# SensorsOnly_v6.net
KiCad netlist of a schematic drawn in EAGLE
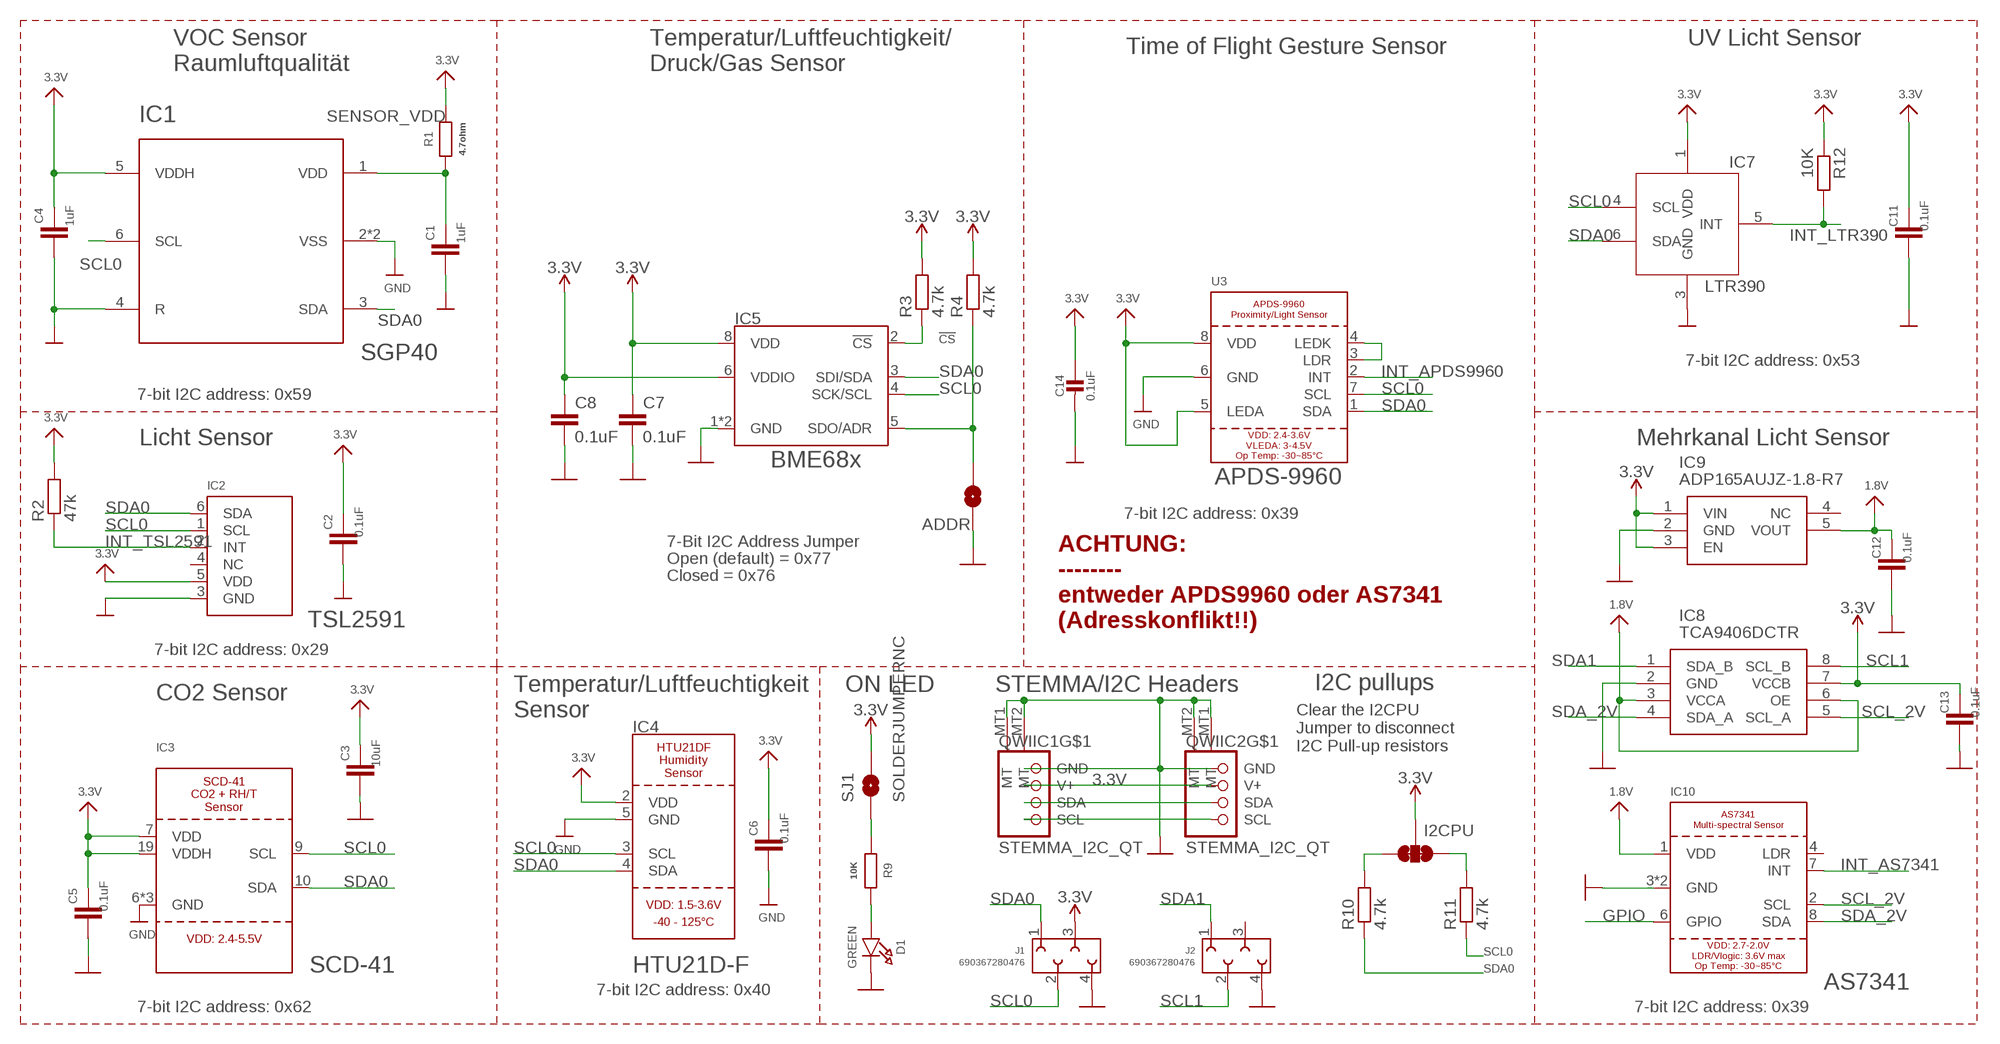
[diagram p0: schematic, sheet 1]

(export (version "E")
  (design (tool "Eeschema 10.0.6"))
  (components
    (comp (ref "ADDR")
      (value "JUMPER-SMT_2_NO_SILK")
      (footprint "eagle-import:SMT-JUMPER_2_NO_SILK")
      (libsource (lib "eagle-import") (part "JUMPER-SMT_2_NO_SILK"))
    )
    (comp (ref "C1")
      (value "1uF")
      (footprint "eagle-import:C0805")
      (libsource (lib "eagle-import") (part "C-EUC0805"))
    )
    (comp (ref "C2")
      (value "0.1uF")
      (footprint "eagle-import:C0603")
      (libsource (lib "eagle-import") (part "C-EUC0603"))
    )
    (comp (ref "C3")
      (value "10uF")
      (footprint "eagle-import:C0805")
      (libsource (lib "eagle-import") (part "C-EUC0805"))
    )
    (comp (ref "C4")
      (value "1uF")
      (footprint "eagle-import:C0805")
      (libsource (lib "eagle-import") (part "C-EUC0805"))
    )
    (comp (ref "C5")
      (value "0.1uF")
      (footprint "eagle-import:C0603")
      (libsource (lib "eagle-import") (part "C-EUC0603"))
    )
    (comp (ref "C6")
      (value "0.1uF")
      (footprint "eagle-import:C0603")
      (libsource (lib "eagle-import") (part "C-EUC0603"))
    )
    (comp (ref "C7")
      (value "0.1uF")
      (footprint "eagle-import:C0603")
      (libsource (lib "eagle-import") (part "C-EUC0603"))
    )
    (comp (ref "C8")
      (value "0.1uF")
      (footprint "eagle-import:C0603")
      (libsource (lib "eagle-import") (part "C-EUC0603"))
    )
    (comp (ref "C11")
      (value "0.1uF")
      (footprint "eagle-import:C0603")
      (libsource (lib "eagle-import") (part "C-EUC0603"))
    )
    (comp (ref "C12")
      (value "0.1uF")
      (footprint "eagle-import:C0603")
      (libsource (lib "eagle-import") (part "C-EUC0603"))
    )
    (comp (ref "C13")
      (value "0.1uF")
      (footprint "eagle-import:C0603")
      (libsource (lib "eagle-import") (part "C-EUC0603"))
    )
    (comp (ref "C14")
      (value "0.1uF")
      (footprint "eagle-import:0603-NO")
      (libsource (lib "eagle-import") (part "CAP_CERAMIC0603_NO"))
    )
    (comp (ref "D1")
      (value "GREEN")
      (footprint "eagle-import:CHIPLED_0603_NOOUTLINE")
      (libsource (lib "eagle-import") (part "LED0603_NOOUTLINE"))
    )
    (comp (ref "I2CPU")
      (value "I2C PU")
      (footprint "eagle-import:SMT-JUMPER_3_2-NC_TRACE_SILK")
      (libsource (lib "eagle-import") (part "JUMPER-SMT_3_2-NC_TRACE_SILK"))
    )
    (comp (ref "IC1")
      (value "SGP40")
      (footprint "eagle-import:SGP30")
      (libsource (lib "eagle-import") (part "SGP30"))
    )
    (comp (ref "IC2")
      (value "TSL2591")
      (footprint "eagle-import:DFN6_TAOS")
      (libsource (lib "eagle-import") (part "LIGHT_TSL2591"))
    )
    (comp (ref "IC3")
      (value "SCD-41")
      (footprint "eagle-import:SCD41")
      (libsource (lib "eagle-import") (part "SCD-41"))
    )
    (comp (ref "IC4")
      (value "HTU21D-F")
      (footprint "eagle-import:HTU21DF")
      (libsource (lib "eagle-import") (part "HTU21DF"))
    )
    (comp (ref "IC5")
      (value "BME680 Air Quality Sensor")
      (footprint "eagle-import:LGA3.0X3.0")
      (libsource (lib "eagle-import") (part "BME680-LGA"))
    )
    (comp (ref "IC7")
      (value "LTR390")
      (footprint "eagle-import:LTR390")
      (libsource (lib "eagle-import") (part "LTR390"))
    )
    (comp (ref "IC8")
      (value "TCA9406DCTR")
      (footprint "eagle-import:SOP65P400X130-8N")
      (fields (field (name "MOUSER_PART_NUMBER") "595-TCA9406DCTR"))
      (libsource (lib "eagle-import") (part "TCA9406DCTR"))
    )
    (comp (ref "IC9")
      (value "ADP165AUJZ-1.8-R7")
      (footprint "eagle-import:SOT95P280X100-5N")
      (fields
        (field (name "MANUFACTURER_PART_NUMBER") "ADP165AUJZ-3.3-R7")
        (field (name "MOUSER_PART_NUMBER") "584-ADP165AUJZ3.3R7")
      )
      (libsource (lib "eagle-import") (part "ADP165AUJZ-3.3-R7"))
    )
    (comp (ref "IC10")
      (value "AS7341")
      (footprint "eagle-import:AS7341")
      (libsource (lib "eagle-import") (part "AS7341"))
    )
    (comp (ref "J1")
      (value "690367280476")
      (footprint "eagle-import:690367280476")
      (libsource (lib "eagle-import") (part "690367280476"))
    )
    (comp (ref "J2")
      (value "690367280476")
      (footprint "eagle-import:690367280476")
      (libsource (lib "eagle-import") (part "690367280476"))
    )
    (comp (ref "QWIIC1")
      (value "STEMMA_I2C_QT")
      (footprint "eagle-import:JST_SH4")
      (libsource (lib "eagle-import") (part "STEMMA_I2C_QT"))
    )
    (comp (ref "QWIIC2")
      (value "STEMMA_I2C_QT")
      (footprint "eagle-import:JST_SH4")
      (libsource (lib "eagle-import") (part "STEMMA_I2C_QT"))
    )
    (comp (ref "R1")
      (value "4.7ohm")
      (footprint "eagle-import:R0603")
      (libsource (lib "eagle-import") (part "R-EU_R0603"))
    )
    (comp (ref "R2")
      (value "47k")
      (footprint "eagle-import:R0603")
      (libsource (lib "eagle-import") (part "R-EU_R0603"))
    )
    (comp (ref "R3")
      (value "4.7k")
      (footprint "eagle-import:R0603")
      (libsource (lib "eagle-import") (part "R-EU_R0603"))
    )
    (comp (ref "R4")
      (value "4.7k")
      (footprint "eagle-import:R0603")
      (libsource (lib "eagle-import") (part "R-EU_R0603"))
    )
    (comp (ref "R9")
      (value "10K")
      (footprint "eagle-import:R0603")
      (libsource (lib "eagle-import") (part "R-EU_R0603"))
    )
    (comp (ref "R10")
      (value "4.7k")
      (footprint "eagle-import:R0603")
      (libsource (lib "eagle-import") (part "R-EU_R0603"))
    )
    (comp (ref "R11")
      (value "4.7k")
      (footprint "eagle-import:R0603")
      (libsource (lib "eagle-import") (part "R-EU_R0603"))
    )
    (comp (ref "R12")
      (value "10K")
      (footprint "eagle-import:R0603")
      (libsource (lib "eagle-import") (part "R-EU_R0603"))
    )
    (comp (ref "SJ1")
      (value "SOLDERJUMPERNC")
      (footprint "eagle-import:SJ_2S")
      (libsource (lib "eagle-import") (part "SOLDERJUMPERNC"))
    )
    (comp (ref "U3")
      (value "APDS-9960")
      (footprint "eagle-import:APDS-9960")
      (libsource (lib "eagle-import") (part "APDS-9960"))
    )
  )
  (nets
    (net (code "1") (name "/GPIO") (class "Default")
      (node (ref "IC10") (pin "6") (pinfunction "GPIO_6") (pintype "power_in"))
    )
    (net (code "2") (name "/INT_APDS9960") (class "Default")
      (node (ref "U3") (pin "2") (pinfunction "INT_2") (pintype "output"))
    )
    (net (code "3") (name "/INT_AS7341") (class "Default")
      (node (ref "IC10") (pin "7") (pinfunction "INT_7") (pintype "output"))
    )
    (net (code "4") (name "/INT_LTR390") (class "Default")
      (node (ref "IC7") (pin "5") (pinfunction "INT_5") (pintype "bidirectional"))
      (node (ref "R12") (pin "2") (pinfunction "2_2") (pintype "passive"))
    )
    (net (code "5") (name "/INT_TSL2591") (class "Default")
      (node (ref "IC2") (pin "2") (pinfunction "INT_2") (pintype "output"))
      (node (ref "R2") (pin "1") (pinfunction "1_1") (pintype "passive"))
    )
    (net (code "6") (name "/SCL1") (class "Default")
      (node (ref "IC8") (pin "8") (pinfunction "SCL_B_8") (pintype "bidirectional"))
      (node (ref "J2") (pin "2") (pinfunction "2_2") (pintype "passive"))
    )
    (net (code "7") (name "/SCL_2V") (class "Default")
      (node (ref "IC10") (pin "2") (pinfunction "SCL_2") (pintype "input"))
      (node (ref "IC8") (pin "5") (pinfunction "SCL_A_5") (pintype "bidirectional"))
    )
    (net (code "8") (name "/SDA1") (class "Default")
      (node (ref "IC8") (pin "1") (pinfunction "SDA_B_1") (pintype "bidirectional"))
      (node (ref "J2") (pin "1") (pinfunction "1_1") (pintype "passive"))
    )
    (net (code "9") (name "/SDA_2V") (class "Default")
      (node (ref "IC10") (pin "8") (pinfunction "SDA_8") (pintype "bidirectional"))
      (node (ref "IC8") (pin "4") (pinfunction "SDA_A_4") (pintype "bidirectional"))
    )
    (net (code "10") (name "/SENSOR_VDD") (class "Default")
      (node (ref "C1") (pin "1") (pinfunction "1_1") (pintype "passive"))
      (node (ref "IC1") (pin "1") (pinfunction "VDD_1") (pintype "bidirectional"))
      (node (ref "R1") (pin "1") (pinfunction "1_1") (pintype "passive"))
    )
    (net (code "11") (name "/~{CS}") (class "Default")
      (node (ref "IC5") (pin "2") (pinfunction "~{CS}_2") (pintype "bidirectional"))
      (node (ref "R3") (pin "1") (pinfunction "1_1") (pintype "passive"))
    )
    (net (code "12") (name "1.8V") (class "Default")
      (node (ref "C12") (pin "1") (pinfunction "1_1") (pintype "passive"))
      (node (ref "IC10") (pin "1") (pinfunction "VDD_1") (pintype "power_in"))
      (node (ref "IC8") (pin "3") (pinfunction "VCCA_3") (pintype "bidirectional"))
      (node (ref "IC8") (pin "6") (pinfunction "OE_6") (pintype "bidirectional"))
      (node (ref "IC9") (pin "5") (pinfunction "VOUT_5") (pintype "bidirectional"))
    )
    (net (code "13") (name "3.3V") (class "Default")
      (node (ref "C11") (pin "1") (pinfunction "1_1") (pintype "passive"))
      (node (ref "C13") (pin "1") (pinfunction "1_1") (pintype "passive"))
      (node (ref "C14") (pin "1") (pinfunction "1_1") (pintype "passive"))
      (node (ref "C2") (pin "1") (pinfunction "1_1") (pintype "passive"))
      (node (ref "C3") (pin "1") (pinfunction "1_1") (pintype "passive"))
      (node (ref "C4") (pin "1") (pinfunction "1_1") (pintype "passive"))
      (node (ref "C5") (pin "1") (pinfunction "1_1") (pintype "passive"))
      (node (ref "C6") (pin "1") (pinfunction "1_1") (pintype "passive"))
      (node (ref "C7") (pin "1") (pinfunction "1_1") (pintype "passive"))
      (node (ref "C8") (pin "1") (pinfunction "1_1") (pintype "passive"))
      (node (ref "I2CPU") (pin "2") (pinfunction "2_2") (pintype "passive"))
      (node (ref "IC1") (pin "5") (pinfunction "VDDH_5") (pintype "bidirectional"))
      (node (ref "IC2") (pin "5") (pinfunction "VDD_5") (pintype "power_in"))
      (node (ref "IC3") (pin "19") (pinfunction "VDDH_19") (pintype "power_in"))
      (node (ref "IC3") (pin "7") (pinfunction "VDD_7") (pintype "power_in"))
      (node (ref "IC4") (pin "2") (pinfunction "VDD_2") (pintype "power_in"))
      (node (ref "IC5") (pin "6") (pinfunction "VDDIO_6") (pintype "bidirectional"))
      (node (ref "IC5") (pin "8") (pinfunction "VDD_8") (pintype "bidirectional"))
      (node (ref "IC7") (pin "1") (pinfunction "VDD_1") (pintype "power_in"))
      (node (ref "IC8") (pin "7") (pinfunction "VCCB_7") (pintype "bidirectional"))
      (node (ref "IC9") (pin "1") (pinfunction "VIN_1") (pintype "bidirectional"))
      (node (ref "IC9") (pin "3") (pinfunction "EN_3") (pintype "bidirectional"))
      (node (ref "J1") (pin "3") (pinfunction "3_3") (pintype "passive"))
      (node (ref "QWIIC1") (pin "2") (pinfunction "V+_2") (pintype "passive"))
      (node (ref "QWIIC2") (pin "2") (pinfunction "V+_2") (pintype "passive"))
      (node (ref "R1") (pin "2") (pinfunction "2_2") (pintype "passive"))
      (node (ref "R12") (pin "1") (pinfunction "1_1") (pintype "passive"))
      (node (ref "R2") (pin "2") (pinfunction "2_2") (pintype "passive"))
      (node (ref "R3") (pin "2") (pinfunction "2_2") (pintype "passive"))
      (node (ref "R4") (pin "2") (pinfunction "2_2") (pintype "passive"))
      (node (ref "SJ1") (pin "2") (pinfunction "2_2") (pintype "passive"))
      (node (ref "U3") (pin "5") (pinfunction "LEDA_5") (pintype "power_in"))
      (node (ref "U3") (pin "8") (pinfunction "VDD_8") (pintype "power_in"))
    )
    (net (code "14") (name "GND") (class "Default")
      (node (ref "ADDR") (pin "1") (pinfunction "1_1") (pintype "passive"))
      (node (ref "C1") (pin "2") (pinfunction "2_2") (pintype "passive"))
      (node (ref "C11") (pin "2") (pinfunction "2_2") (pintype "passive"))
      (node (ref "C12") (pin "2") (pinfunction "2_2") (pintype "passive"))
      (node (ref "C13") (pin "2") (pinfunction "2_2") (pintype "passive"))
      (node (ref "C14") (pin "2") (pinfunction "2_2") (pintype "passive"))
      (node (ref "C2") (pin "2") (pinfunction "2_2") (pintype "passive"))
      (node (ref "C3") (pin "2") (pinfunction "2_2") (pintype "passive"))
      (node (ref "C4") (pin "2") (pinfunction "2_2") (pintype "passive"))
      (node (ref "C5") (pin "2") (pinfunction "2_2") (pintype "passive"))
      (node (ref "C6") (pin "2") (pinfunction "2_2") (pintype "passive"))
      (node (ref "C7") (pin "2") (pinfunction "2_2") (pintype "passive"))
      (node (ref "C8") (pin "2") (pinfunction "2_2") (pintype "passive"))
      (node (ref "D1") (pin "C") (pinfunction "C_C") (pintype "passive"))
      (node (ref "IC1") (pin "2") (pinfunction "VSS_2") (pintype "bidirectional"))
      (node (ref "IC1") (pin "4") (pinfunction "R_4") (pintype "bidirectional"))
      (node (ref "IC1") (pin "P$7") (pinfunction "VSS_P$7") (pintype "bidirectional"))
      (node (ref "IC10") (pin "3") (pinfunction "GND_3") (pintype "power_in"))
      (node (ref "IC10") (pin "5") (pinfunction "GND_5") (pintype "power_in"))
      (node (ref "IC2") (pin "3") (pinfunction "GND_3") (pintype "power_in"))
      (node (ref "IC3") (pin "20") (pinfunction "GND_20") (pintype "power_in"))
      (node (ref "IC3") (pin "6") (pinfunction "GND_6") (pintype "power_in"))
      (node (ref "IC3") (pin "P$1") (pinfunction "GND_P$1") (pintype "power_in"))
      (node (ref "IC4") (pin "5") (pinfunction "GND_5") (pintype "power_in"))
      (node (ref "IC5") (pin "1") (pinfunction "GND_1") (pintype "bidirectional"))
      (node (ref "IC5") (pin "7") (pinfunction "GND_7") (pintype "bidirectional"))
      (node (ref "IC7") (pin "3") (pinfunction "GND_3") (pintype "power_in"))
      (node (ref "IC8") (pin "2") (pinfunction "GND_2") (pintype "bidirectional"))
      (node (ref "IC9") (pin "2") (pinfunction "GND_2") (pintype "bidirectional"))
      (node (ref "J1") (pin "4") (pinfunction "4_4") (pintype "passive"))
      (node (ref "J2") (pin "4") (pinfunction "4_4") (pintype "passive"))
      (node (ref "QWIIC1") (pin "1") (pinfunction "GND_1") (pintype "passive"))
      (node (ref "QWIIC1") (pin "MT1") (pinfunction "MT_MT1") (pintype "bidirectional"))
      (node (ref "QWIIC1") (pin "MT2") (pinfunction "MT_MT2") (pintype "bidirectional"))
      (node (ref "QWIIC2") (pin "1") (pinfunction "GND_1") (pintype "passive"))
      (node (ref "QWIIC2") (pin "MT1") (pinfunction "MT_MT1") (pintype "bidirectional"))
      (node (ref "QWIIC2") (pin "MT2") (pinfunction "MT_MT2") (pintype "bidirectional"))
      (node (ref "U3") (pin "6") (pinfunction "GND_6") (pintype "power_in"))
    )
    (net (code "15") (name "Net-(D1-PadA)") (class "Default")
      (node (ref "D1") (pin "A") (pinfunction "A_A") (pintype "passive"))
      (node (ref "R9") (pin "2") (pinfunction "2_2") (pintype "passive"))
    )
    (net (code "16") (name "Net-(I2CPU-Pad1)") (class "Default")
      (node (ref "I2CPU") (pin "1") (pinfunction "1_1") (pintype "passive"))
      (node (ref "R11") (pin "2") (pinfunction "2_2") (pintype "passive"))
    )
    (net (code "17") (name "Net-(I2CPU-Pad3)") (class "Default")
      (node (ref "I2CPU") (pin "3") (pinfunction "3_3") (pintype "passive"))
      (node (ref "R10") (pin "2") (pinfunction "2_2") (pintype "passive"))
    )
    (net (code "18") (name "Net-(IC5-SDO{slash}ADR)") (class "Default")
      (node (ref "ADDR") (pin "2") (pinfunction "2_2") (pintype "passive"))
      (node (ref "IC5") (pin "5") (pinfunction "SDO/ADR_5") (pintype "bidirectional"))
      (node (ref "R4") (pin "1") (pinfunction "1_1") (pintype "passive"))
    )
    (net (code "19") (name "Net-(R9-Pad1)") (class "Default")
      (node (ref "R9") (pin "1") (pinfunction "1_1") (pintype "passive"))
      (node (ref "SJ1") (pin "1") (pinfunction "1_1") (pintype "passive"))
    )
    (net (code "20") (name "Net-(U3-LDR)") (class "Default")
      (node (ref "U3") (pin "3") (pinfunction "LDR_3") (pintype "bidirectional"))
      (node (ref "U3") (pin "4") (pinfunction "LEDK_4") (pintype "bidirectional"))
    )
    (net (code "21") (name "SCL0") (class "Default")
      (node (ref "IC1") (pin "6") (pinfunction "SCL_6") (pintype "bidirectional"))
      (node (ref "IC2") (pin "1") (pinfunction "SCL_1") (pintype "bidirectional"))
      (node (ref "IC3") (pin "9") (pinfunction "SCL_9") (pintype "input"))
      (node (ref "IC4") (pin "3") (pinfunction "SCL_3") (pintype "input"))
      (node (ref "IC5") (pin "4") (pinfunction "SCK/SCL_4") (pintype "bidirectional"))
      (node (ref "IC7") (pin "4") (pinfunction "SCL_4") (pintype "bidirectional"))
      (node (ref "J1") (pin "2") (pinfunction "2_2") (pintype "passive"))
      (node (ref "QWIIC1") (pin "4") (pinfunction "SCL_4") (pintype "passive"))
      (node (ref "QWIIC2") (pin "4") (pinfunction "SCL_4") (pintype "passive"))
      (node (ref "R11") (pin "1") (pinfunction "1_1") (pintype "passive"))
      (node (ref "U3") (pin "7") (pinfunction "SCL_7") (pintype "input"))
    )
    (net (code "22") (name "SDA0") (class "Default")
      (node (ref "IC1") (pin "3") (pinfunction "SDA_3") (pintype "bidirectional"))
      (node (ref "IC2") (pin "6") (pinfunction "SDA_6") (pintype "bidirectional"))
      (node (ref "IC3") (pin "10") (pinfunction "SDA_10") (pintype "bidirectional"))
      (node (ref "IC4") (pin "4") (pinfunction "SDA_4") (pintype "bidirectional"))
      (node (ref "IC5") (pin "3") (pinfunction "SDI/SDA_3") (pintype "bidirectional"))
      (node (ref "IC7") (pin "6") (pinfunction "SDA_6") (pintype "bidirectional"))
      (node (ref "J1") (pin "1") (pinfunction "1_1") (pintype "passive"))
      (node (ref "QWIIC1") (pin "3") (pinfunction "SDA_3") (pintype "passive"))
      (node (ref "QWIIC2") (pin "3") (pinfunction "SDA_3") (pintype "passive"))
      (node (ref "R10") (pin "1") (pinfunction "1_1") (pintype "passive"))
      (node (ref "U3") (pin "1") (pinfunction "SDA_1") (pintype "bidirectional"))
    )
    (net (code "23") (name "unconnected-(IC2-NC-Pad4)") (class "Default")
      (node (ref "IC2") (pin "4") (pinfunction "NC_4") (pintype "no_connect"))
    )
    (net (code "24") (name "unconnected-(IC9-NC-Pad4)") (class "Default")
      (node (ref "IC9") (pin "4") (pinfunction "NC_4") (pintype "no_connect"))
    )
    (net (code "25") (name "unconnected-(IC10-LDR-Pad4)") (class "Default")
      (node (ref "IC10") (pin "4") (pinfunction "LDR_4") (pintype "bidirectional"))
    )
    (net (code "26") (name "unconnected-(J2-Pad3)") (class "Default")
      (node (ref "J2") (pin "3") (pinfunction "3_3") (pintype "passive"))
    )
  )
)
